# kuzgunv2_0.net
KiCad netlist of a schematic drawn in Altium Designer
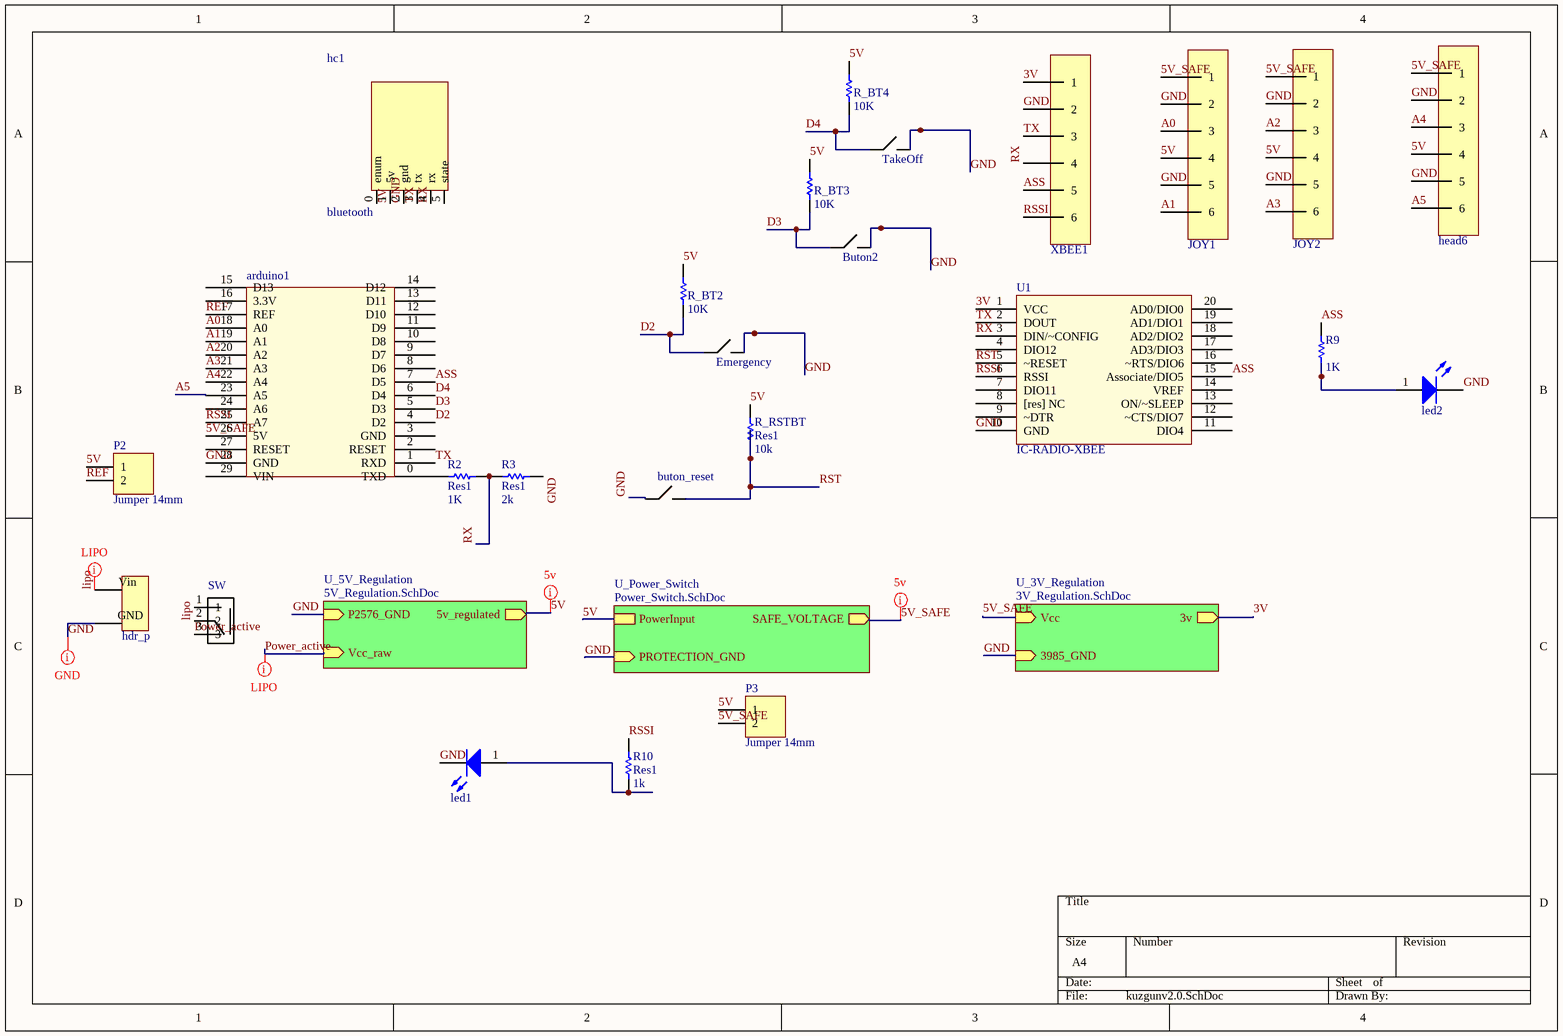
[diagram p0: kuzgunv2.0.SchDoc]

(export (version "E")
  (design (tool "Eeschema 10.0.6"))
  (components
    (comp (ref "arduino1")
      (value "arduinoNano")
      (footprint "Arduino nano")
      (libsource (lib "nanoArduino") (part "arduinoNano"))
    )
    (comp (ref "Buton2") (value "buton") (footprint "4pin_smd") (libsource (lib "") (part "buton_2")))
    (comp (ref "buton_reset")
      (value "buton")
      (footprint "4pin_smd")
      (libsource (lib "resistance") (part "buton"))
    )
    (comp (ref "Emergency") (value "buton") (footprint "4pin_smd") (libsource (lib "") (part "buton_1")))
    (comp (ref "hc1")
      (value "bluetooth")
      (footprint "hc05")
      (description "bluetooth device hc 05")
      (libsource (lib "hc05") (part "hc05"))
    )
    (comp (ref "hdr_p")
      (value "header_2_power")
      (footprint "HDR2_POWER")
      (libsource (lib "headers") (part "header_2_power"))
    )
    (comp (ref "head6")
      (value "header_6")
      (footprint "hdr_6pin")
      (libsource (lib "headers") (part "header_6"))
    )
    (comp (ref "JOY1")
      (value "header_6")
      (footprint "hdr_6pin")
      (libsource (lib "headers") (part "header_6"))
    )
    (comp (ref "JOY2")
      (value "header_6")
      (footprint "hdr_6pin")
      (libsource (lib "headers") (part "header_6"))
    )
    (comp (ref "led1")
      (value "L_green")
      (footprint "Led_green")
      (libsource (lib "Led_edited") (part "L_green"))
    )
    (comp (ref "led2")
      (value "L_green")
      (footprint "Led_green")
      (libsource (lib "Led_edited") (part "L_green"))
    )
    (comp (ref "P2")
      (value "Jumper 14mm")
      (footprint "jumper2pin_1.27")
      (description "Jumper 14MM")
      (fields (field (name "PUBLISHER") "Altium Limited"))
      (libsource (lib "headers") (part "Jumper 14mm"))
    )
    (comp (ref "P3")
      (value "Jumper 14mm")
      (footprint "jumper2pin_1.27")
      (description "Jumper 14MM")
      (fields (field (name "PUBLISHER") "Altium Limited"))
      (libsource (lib "headers") (part "Jumper 14mm"))
    )
    (comp (ref "R1")
      (value "R_BT4")
      (footprint "led")
      (description "Resistor")
      (fields (field (name "ALTIUM_VALUE") "10K") (field (name "PUBLISHER") "Altium Limited"))
      (libsource (lib "Miscellaneous Devices") (part "Res1"))
    )
    (comp (ref "R2")
      (value "Res1")
      (footprint "led")
      (description "Resistor")
      (fields (field (name "ALTIUM_VALUE") "1K") (field (name "PUBLISHER") "Altium Limited"))
      (libsource (lib "Miscellaneous Devices") (part "Res1"))
    )
    (comp (ref "R3")
      (value "Res1")
      (footprint "led")
      (description "Resistor")
      (fields (field (name "ALTIUM_VALUE") "2k") (field (name "PUBLISHER") "Altium Limited"))
      (libsource (lib "Miscellaneous Devices") (part "Res1"))
    )
    (comp (ref "R4")
      (value "R_BT3")
      (footprint "led")
      (description "Resistor")
      (fields (field (name "ALTIUM_VALUE") "10K") (field (name "PUBLISHER") "Altium Limited"))
      (libsource (lib "Miscellaneous Devices") (part "Res1"))
    )
    (comp (ref "R5")
      (value "R_BT2")
      (footprint "led")
      (description "Resistor")
      (fields (field (name "ALTIUM_VALUE") "10K") (field (name "PUBLISHER") "Altium Limited"))
      (libsource (lib "Miscellaneous Devices") (part "Res1"))
    )
    (comp (ref "R9")
      (value "1K")
      (footprint "led")
      (description "Resistor")
      (fields (field (name "Comment") "Res1") (field (name "PUBLISHER") "Altium Limited"))
      (libsource (lib "Miscellaneous Devices") (part "Res1"))
    )
    (comp (ref "R10")
      (value "Res1")
      (footprint "led")
      (description "Resistor")
      (fields (field (name "ALTIUM_VALUE") "1k") (field (name "PUBLISHER") "Altium Limited"))
      (libsource (lib "Miscellaneous Devices") (part "Res1"))
    )
    (comp (ref "R_RSTBT")
      (value "Res1")
      (footprint "led")
      (description "Resistor")
      (fields (field (name "ALTIUM_VALUE") "10k") (field (name "PUBLISHER") "Altium Limited"))
      (libsource (lib "Miscellaneous Devices") (part "Res1"))
    )
    (comp (ref "SW")
      (value "Master_S")
      (footprint "SW")
      (description "Switch Slide ON ON SPDT Top Slide 0.1A 12VDC 10000Cycles PC Pins Thru-Hole Bulk")
      (fields (field (name "MF") "C&K Components"))
      (libsource (lib "slide_switch") (part "Master_S"))
    )
    (comp (ref "TakeOff")
      (value "buton")
      (footprint "4pin_smd")
      (libsource (lib "resistance") (part "buton"))
    )
    (comp (ref "U1")
      (value "IC-RADIO-XBEE")
      (footprint "XBee Standard")
      (description "CONN XBEE TH")
      (libsource (lib "XBEE") (part "IC-RADIO-XBEE"))
    )
    (comp (ref "XBEE1")
      (value "header_6")
      (footprint "hdr6_1.27")
      (libsource (lib "headers") (part "header_6"))
    )
  )
  (nets
    (net (code "1") (name "/3V") (class "Default")
      (node (ref "U1") (pin "1") (pinfunction "VCC_1") (pintype "passive"))
      (node (ref "XBEE1") (pin "1") (pinfunction "1_1") (pintype "passive"))
    )
    (net (code "2") (name "/5V") (class "Default")
      (node (ref "JOY1") (pin "4") (pinfunction "4_4") (pintype "passive"))
      (node (ref "JOY2") (pin "4") (pinfunction "4_4") (pintype "passive"))
      (node (ref "P2") (pin "1") (pinfunction "1_1") (pintype "passive"))
      (node (ref "P3") (pin "1") (pinfunction "1_1") (pintype "passive"))
      (node (ref "R1") (pin "2") (pinfunction "2_2") (pintype "passive"))
      (node (ref "R4") (pin "2") (pinfunction "2_2") (pintype "passive"))
      (node (ref "R5") (pin "2") (pinfunction "2_2") (pintype "passive"))
      (node (ref "R_RSTBT") (pin "2") (pinfunction "2_2") (pintype "passive"))
      (node (ref "hc1") (pin "1") (pinfunction "5v_1") (pintype "passive"))
      (node (ref "head6") (pin "4") (pinfunction "4_4") (pintype "passive"))
    )
    (net (code "3") (name "/5V_SAFE") (class "Default")
      (node (ref "JOY1") (pin "1") (pinfunction "1_1") (pintype "passive"))
      (node (ref "JOY2") (pin "1") (pinfunction "1_1") (pintype "passive"))
      (node (ref "P3") (pin "2") (pinfunction "2_2") (pintype "passive"))
      (node (ref "arduino1") (pin "26") (pinfunction "5V_26") (pintype "passive"))
      (node (ref "head6") (pin "1") (pinfunction "1_1") (pintype "passive"))
    )
    (net (code "5") (name "/A0") (class "Default")
      (node (ref "JOY1") (pin "3") (pinfunction "3_3") (pintype "passive"))
      (node (ref "arduino1") (pin "18") (pinfunction "A0_18") (pintype "passive"))
    )
    (net (code "6") (name "/A1") (class "Default")
      (node (ref "JOY1") (pin "6") (pinfunction "6_6") (pintype "passive"))
      (node (ref "arduino1") (pin "19") (pinfunction "A1_19") (pintype "passive"))
    )
    (net (code "7") (name "/A2") (class "Default")
      (node (ref "JOY2") (pin "3") (pinfunction "3_3") (pintype "passive"))
      (node (ref "arduino1") (pin "20") (pinfunction "A2_20") (pintype "passive"))
    )
    (net (code "8") (name "/A3") (class "Default")
      (node (ref "JOY2") (pin "6") (pinfunction "6_6") (pintype "passive"))
      (node (ref "arduino1") (pin "21") (pinfunction "A3_21") (pintype "passive"))
    )
    (net (code "9") (name "/A4") (class "Default")
      (node (ref "arduino1") (pin "22") (pinfunction "A4_22") (pintype "passive"))
      (node (ref "head6") (pin "3") (pinfunction "3_3") (pintype "passive"))
    )
    (net (code "10") (name "/A5") (class "Default")
      (node (ref "arduino1") (pin "23") (pinfunction "A5_23") (pintype "passive"))
      (node (ref "head6") (pin "6") (pinfunction "6_6") (pintype "passive"))
    )
    (net (code "11") (name "/ASS") (class "Default")
      (node (ref "R9") (pin "2") (pinfunction "2_2") (pintype "passive"))
      (node (ref "U1") (pin "15") (pinfunction "Associate/DIO5_15") (pintype "passive"))
      (node (ref "XBEE1") (pin "5") (pinfunction "5_5") (pintype "passive"))
      (node (ref "arduino1") (pin "7") (pinfunction "D5_7") (pintype "passive"))
    )
    (net (code "12") (name "/D2") (class "Default")
      (node (ref "Emergency") (pin "1") (pinfunction "1_1") (pintype "passive"))
      (node (ref "R5") (pin "1") (pinfunction "1_1") (pintype "passive"))
      (node (ref "arduino1") (pin "4") (pinfunction "D2_4") (pintype "passive"))
    )
    (net (code "13") (name "/D3") (class "Default")
      (node (ref "Buton2") (pin "1") (pinfunction "1_1") (pintype "passive"))
      (node (ref "R4") (pin "1") (pinfunction "1_1") (pintype "passive"))
      (node (ref "arduino1") (pin "5") (pinfunction "D3_5") (pintype "passive"))
    )
    (net (code "14") (name "/D4") (class "Default")
      (node (ref "R1") (pin "1") (pinfunction "1_1") (pintype "passive"))
      (node (ref "TakeOff") (pin "1") (pinfunction "1_1") (pintype "passive"))
      (node (ref "arduino1") (pin "6") (pinfunction "D4_6") (pintype "passive"))
    )
    (net (code "15") (name "/GND") (class "Default")
      (node (ref "Buton2") (pin "2") (pinfunction "2_2") (pintype "passive"))
      (node (ref "Emergency") (pin "2") (pinfunction "2_2") (pintype "passive"))
      (node (ref "JOY1") (pin "2") (pinfunction "2_2") (pintype "passive"))
      (node (ref "JOY1") (pin "5") (pinfunction "5_5") (pintype "passive"))
      (node (ref "JOY2") (pin "2") (pinfunction "2_2") (pintype "passive"))
      (node (ref "JOY2") (pin "5") (pinfunction "5_5") (pintype "passive"))
      (node (ref "R3") (pin "1") (pinfunction "1_1") (pintype "passive"))
      (node (ref "TakeOff") (pin "2") (pinfunction "2_2") (pintype "passive"))
      (node (ref "U1") (pin "10") (pinfunction "GND_10") (pintype "passive"))
      (node (ref "XBEE1") (pin "2") (pinfunction "2_2") (pintype "passive"))
      (node (ref "arduino1") (pin "28") (pinfunction "GND_28") (pintype "passive"))
      (node (ref "buton_reset") (pin "1") (pinfunction "1_1") (pintype "passive"))
      (node (ref "hc1") (pin "2") (pinfunction "gnd_2") (pintype "passive"))
      (node (ref "hdr_p") (pin "GND") (pinfunction "2_GND") (pintype "passive"))
      (node (ref "head6") (pin "2") (pinfunction "2_2") (pintype "passive"))
      (node (ref "head6") (pin "5") (pinfunction "5_5") (pintype "passive"))
      (node (ref "led1") (pin "2") (pinfunction "K_2") (pintype "passive"))
      (node (ref "led2") (pin "2") (pinfunction "K_2") (pintype "passive"))
    )
    (net (code "16") (name "/Power_active") (class "Default")
      (node (ref "SW") (pin "3") (pinfunction "3_3") (pintype "passive"))
    )
    (net (code "17") (name "/REF") (class "Default")
      (node (ref "P2") (pin "2") (pinfunction "2_2") (pintype "passive"))
      (node (ref "arduino1") (pin "17") (pinfunction "REF_17") (pintype "passive"))
    )
    (net (code "18") (name "/RSSI") (class "Default")
      (node (ref "R10") (pin "2") (pinfunction "2_2") (pintype "passive"))
      (node (ref "U1") (pin "6") (pinfunction "RSSI_6") (pintype "passive"))
      (node (ref "XBEE1") (pin "6") (pinfunction "6_6") (pintype "passive"))
      (node (ref "arduino1") (pin "25") (pinfunction "A7_25") (pintype "passive"))
    )
    (net (code "19") (name "/RST") (class "Default")
      (node (ref "R_RSTBT") (pin "1") (pinfunction "1_1") (pintype "passive"))
      (node (ref "U1") (pin "5") (pinfunction "~RESET_5") (pintype "passive"))
      (node (ref "buton_reset") (pin "2") (pinfunction "2_2") (pintype "passive"))
    )
    (net (code "20") (name "/RX") (class "Default")
      (node (ref "R2") (pin "2") (pinfunction "2_2") (pintype "passive"))
      (node (ref "R3") (pin "2") (pinfunction "2_2") (pintype "passive"))
      (node (ref "U1") (pin "3") (pinfunction "DIN/~CONFIG_3") (pintype "passive"))
      (node (ref "XBEE1") (pin "4") (pinfunction "4_4") (pintype "passive"))
      (node (ref "hc1") (pin "4") (pinfunction "rx_4") (pintype "passive"))
    )
    (net (code "21") (name "/TX") (class "Default")
      (node (ref "U1") (pin "2") (pinfunction "DOUT_2") (pintype "passive"))
      (node (ref "XBEE1") (pin "3") (pinfunction "3_3") (pintype "passive"))
      (node (ref "arduino1") (pin "1") (pinfunction "RXD_1") (pintype "passive"))
      (node (ref "hc1") (pin "3") (pinfunction "tx_3") (pintype "passive"))
    )
    (net (code "22") (name "/lipo") (class "Default")
      (node (ref "SW") (pin "2") (pinfunction "2_2") (pintype "passive"))
      (node (ref "hdr_p") (pin "Vin") (pinfunction "1_Vin") (pintype "passive"))
    )
    (net (code "23") (name "Net-(arduino1-TXD)") (class "Default")
      (node (ref "R2") (pin "1") (pinfunction "1_1") (pintype "passive"))
      (node (ref "arduino1") (pin "0") (pinfunction "TXD_0") (pintype "passive"))
    )
    (net (code "24") (name "Net-(led1-V)") (class "Default")
      (node (ref "R10") (pin "1") (pinfunction "1_1") (pintype "passive"))
      (node (ref "led1") (pin "1") (pinfunction "V_1") (pintype "passive"))
    )
    (net (code "25") (name "Net-(led2-V)") (class "Default")
      (node (ref "R9") (pin "1") (pinfunction "1_1") (pintype "passive"))
      (node (ref "led2") (pin "1") (pinfunction "V_1") (pintype "passive"))
    )
    (net (code "26") (name "unconnected-(SW-Pad1)") (class "Default")
      (node (ref "SW") (pin "1") (pinfunction "1_1") (pintype "passive"))
    )
    (net (code "27") (name "unconnected-(U1-AD0{slash}DIO0-Pad20)") (class "Default")
      (node (ref "U1") (pin "20") (pinfunction "AD0/DIO0_20") (pintype "passive"))
    )
    (net (code "28") (name "unconnected-(U1-AD1{slash}DIO1-Pad19)") (class "Default")
      (node (ref "U1") (pin "19") (pinfunction "AD1/DIO1_19") (pintype "passive"))
    )
    (net (code "29") (name "unconnected-(U1-AD2{slash}DIO2-Pad18)") (class "Default")
      (node (ref "U1") (pin "18") (pinfunction "AD2/DIO2_18") (pintype "passive"))
    )
    (net (code "30") (name "unconnected-(U1-AD3{slash}DIO3-Pad17)") (class "Default")
      (node (ref "U1") (pin "17") (pinfunction "AD3/DIO3_17") (pintype "passive"))
    )
    (net (code "31") (name "unconnected-(U1-DIO4-Pad11)") (class "Default")
      (node (ref "U1") (pin "11") (pinfunction "DIO4_11") (pintype "passive"))
    )
    (net (code "32") (name "unconnected-(U1-DIO11-Pad7)") (class "Default")
      (node (ref "U1") (pin "7") (pinfunction "DIO11_7") (pintype "passive"))
    )
    (net (code "33") (name "unconnected-(U1-DIO12-Pad4)") (class "Default")
      (node (ref "U1") (pin "4") (pinfunction "DIO12_4") (pintype "passive"))
    )
    (net (code "34") (name "unconnected-(U1-ON{slash}~SLEEP-Pad13)") (class "Default")
      (node (ref "U1") (pin "13") (pinfunction "ON/~SLEEP_13") (pintype "passive"))
    )
    (net (code "35") (name "unconnected-(U1-VREF-Pad14)") (class "Default")
      (node (ref "U1") (pin "14") (pinfunction "VREF_14") (pintype "passive"))
    )
    (net (code "36") (name "unconnected-(U1-[res]_NC-Pad8)") (class "Default")
      (node (ref "U1") (pin "8") (pinfunction "[res]_NC_8") (pintype "passive"))
    )
    (net (code "37") (name "unconnected-(U1-~CTS{slash}DIO7-Pad12)") (class "Default")
      (node (ref "U1") (pin "12") (pinfunction "~CTS/DIO7_12") (pintype "passive"))
    )
    (net (code "38") (name "unconnected-(U1-~DTR-Pad9)") (class "Default")
      (node (ref "U1") (pin "9") (pinfunction "~DTR_9") (pintype "passive"))
    )
    (net (code "39") (name "unconnected-(U1-~RTS{slash}DIO6-Pad16)") (class "Default")
      (node (ref "U1") (pin "16") (pinfunction "~RTS/DIO6_16") (pintype "passive"))
    )
    (net (code "40") (name "unconnected-(arduino1-3.3V-Pad16)") (class "Default")
      (node (ref "arduino1") (pin "16") (pinfunction "3.3V_16") (pintype "passive"))
    )
    (net (code "41") (name "unconnected-(arduino1-A6-Pad24)") (class "Default")
      (node (ref "arduino1") (pin "24") (pinfunction "A6_24") (pintype "passive"))
    )
    (net (code "42") (name "unconnected-(arduino1-D6-Pad8)") (class "Default")
      (node (ref "arduino1") (pin "8") (pinfunction "D6_8") (pintype "passive"))
    )
    (net (code "43") (name "unconnected-(arduino1-D7-Pad9)") (class "Default")
      (node (ref "arduino1") (pin "9") (pinfunction "D7_9") (pintype "passive"))
    )
    (net (code "44") (name "unconnected-(arduino1-D8-Pad10)") (class "Default")
      (node (ref "arduino1") (pin "10") (pinfunction "D8_10") (pintype "passive"))
    )
    (net (code "45") (name "unconnected-(arduino1-D9-Pad11)") (class "Default")
      (node (ref "arduino1") (pin "11") (pinfunction "D9_11") (pintype "passive"))
    )
    (net (code "46") (name "unconnected-(arduino1-D10-Pad12)") (class "Default")
      (node (ref "arduino1") (pin "12") (pinfunction "D10_12") (pintype "passive"))
    )
    (net (code "47") (name "unconnected-(arduino1-D11-Pad13)") (class "Default")
      (node (ref "arduino1") (pin "13") (pinfunction "D11_13") (pintype "passive"))
    )
    (net (code "48") (name "unconnected-(arduino1-D12-Pad14)") (class "Default")
      (node (ref "arduino1") (pin "14") (pinfunction "D12_14") (pintype "passive"))
    )
    (net (code "49") (name "unconnected-(arduino1-D13-Pad15)") (class "Default")
      (node (ref "arduino1") (pin "15") (pinfunction "D13_15") (pintype "passive"))
    )
    (net (code "50") (name "unconnected-(arduino1-GND-Pad3)") (class "Default")
      (node (ref "arduino1") (pin "3") (pinfunction "GND_3") (pintype "passive"))
    )
    (net (code "51") (name "unconnected-(arduino1-RESET-Pad2)") (class "Default")
      (node (ref "arduino1") (pin "2") (pinfunction "RESET_2") (pintype "passive"))
    )
    (net (code "52") (name "unconnected-(arduino1-RESET-Pad27)") (class "Default")
      (node (ref "arduino1") (pin "27") (pinfunction "RESET_27") (pintype "passive"))
    )
    (net (code "53") (name "unconnected-(arduino1-VIN-Pad29)") (class "Default")
      (node (ref "arduino1") (pin "29") (pinfunction "VIN_29") (pintype "passive"))
    )
    (net (code "54") (name "unconnected-(hc1-enum-Pad0)") (class "Default")
      (node (ref "hc1") (pin "0") (pinfunction "enum_0") (pintype "passive"))
    )
    (net (code "55") (name "unconnected-(hc1-state-Pad5)") (class "Default")
      (node (ref "hc1") (pin "5") (pinfunction "state_5") (pintype "passive"))
    )
  )
)
